# OLED.net
KiCad netlist of a schematic drawn in Altium Designer
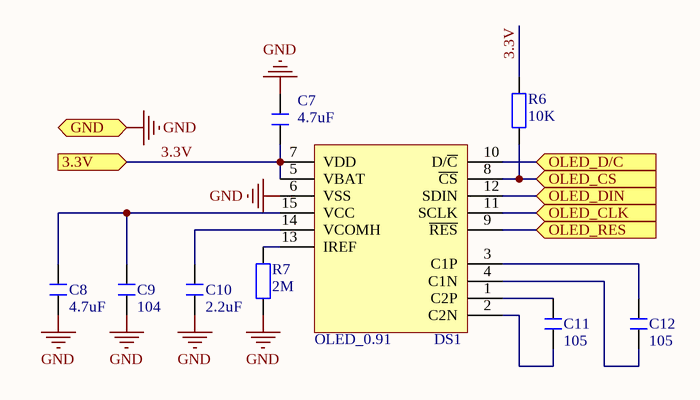
[diagram p0: OLED.SchDoc]

(export (version "E")
  (design (tool "Eeschema 10.0.6"))
  (components
    (comp (ref "C7")
      (value "4.7uF")
      (footprint "C 0603_L")
      (description "贴片电容")
      (libsource (lib "0.1 - 电阻-电容-电感") (part "C"))
    )
    (comp (ref "C8")
      (value "4.7uF")
      (footprint "C 0603_L")
      (description "贴片电容")
      (libsource (lib "0.1 - 电阻-电容-电感") (part "C"))
    )
    (comp (ref "C9")
      (value "104")
      (footprint "C 0603_L")
      (description "贴片电容")
      (libsource (lib "0.1 - 电阻-电容-电感") (part "C"))
    )
    (comp (ref "C10")
      (value "2.2uF")
      (footprint "C 0603_L")
      (description "贴片电容")
      (libsource (lib "0.1 - 电阻-电容-电感") (part "C"))
    )
    (comp (ref "C11")
      (value "105")
      (footprint "C 0603_L")
      (description "贴片电容")
      (libsource (lib "0.1 - 电阻-电容-电感") (part "C"))
    )
    (comp (ref "C12")
      (value "105")
      (footprint "C 0603_L")
      (description "贴片电容")
      (libsource (lib "0.1 - 电阻-电容-电感") (part "C"))
    )
    (comp (ref "DS1") (value "OLED_0.91") (footprint "OLED_0.91") (libsource (lib "显示器件") (part "OLED_0.91")))
    (comp (ref "R6")
      (value "10K")
      (footprint "R 0603_L")
      (description "贴片电阻")
      (libsource (lib "0.1 - 电阻-电容-电感") (part "R"))
    )
    (comp (ref "R7")
      (value "2M")
      (footprint "R 0603_L")
      (description "贴片电阻")
      (libsource (lib "0.1 - 电阻-电容-电感") (part "R"))
    )
  )
  (nets
    (net (code "1") (name "/3.3V") (class "Default")
      (node (ref "C7") (pin "1") (pinfunction "1_1") (pintype "passive"))
      (node (ref "DS1") (pin "5") (pinfunction "VBAT_5") (pintype "passive"))
      (node (ref "DS1") (pin "7") (pinfunction "VDD_7") (pintype "passive"))
      (node (ref "R6") (pin "2") (pinfunction "2_2") (pintype "passive"))
    )
    (net (code "2") (name "/OLED_CLK") (class "Default")
      (node (ref "DS1") (pin "11") (pinfunction "SCLK_11") (pintype "passive"))
    )
    (net (code "3") (name "/OLED_CS") (class "Default")
      (node (ref "DS1") (pin "8") (pinfunction "~{CS}_8") (pintype "passive"))
      (node (ref "R6") (pin "1") (pinfunction "1_1") (pintype "passive"))
    )
    (net (code "4") (name "/OLED_DIN") (class "Default")
      (node (ref "DS1") (pin "12") (pinfunction "SDIN_12") (pintype "passive"))
    )
    (net (code "5") (name "/OLED_D{slash}C") (class "Default")
      (node (ref "DS1") (pin "10") (pinfunction "D/~{C}_10") (pintype "passive"))
    )
    (net (code "6") (name "/OLED_RES") (class "Default")
      (node (ref "DS1") (pin "9") (pinfunction "~{RES}_9") (pintype "passive"))
    )
    (net (code "7") (name "GND") (class "Default")
      (node (ref "C10") (pin "1") (pinfunction "1_1") (pintype "passive"))
      (node (ref "C7") (pin "2") (pinfunction "2_2") (pintype "passive"))
      (node (ref "C8") (pin "1") (pinfunction "1_1") (pintype "passive"))
      (node (ref "C9") (pin "1") (pinfunction "1_1") (pintype "passive"))
      (node (ref "DS1") (pin "6") (pinfunction "VSS_6") (pintype "passive"))
      (node (ref "R7") (pin "1") (pinfunction "1_1") (pintype "passive"))
    )
    (net (code "8") (name "Net-(DS1-C1N)") (class "Default")
      (node (ref "C12") (pin "2") (pinfunction "2_2") (pintype "passive"))
      (node (ref "DS1") (pin "4") (pinfunction "C1N_4") (pintype "passive"))
    )
    (net (code "9") (name "Net-(DS1-C1P)") (class "Default")
      (node (ref "C12") (pin "1") (pinfunction "1_1") (pintype "passive"))
      (node (ref "DS1") (pin "3") (pinfunction "C1P_3") (pintype "passive"))
    )
    (net (code "10") (name "Net-(DS1-C2N)") (class "Default")
      (node (ref "C11") (pin "2") (pinfunction "2_2") (pintype "passive"))
      (node (ref "DS1") (pin "2") (pinfunction "C2N_2") (pintype "passive"))
    )
    (net (code "11") (name "Net-(DS1-C2P)") (class "Default")
      (node (ref "C11") (pin "1") (pinfunction "1_1") (pintype "passive"))
      (node (ref "DS1") (pin "1") (pinfunction "C2P_1") (pintype "passive"))
    )
    (net (code "12") (name "Net-(DS1-IREF)") (class "Default")
      (node (ref "DS1") (pin "13") (pinfunction "IREF_13") (pintype "passive"))
      (node (ref "R7") (pin "2") (pinfunction "2_2") (pintype "passive"))
    )
    (net (code "13") (name "Net-(DS1-VCC)") (class "Default")
      (node (ref "C8") (pin "2") (pinfunction "2_2") (pintype "passive"))
      (node (ref "C9") (pin "2") (pinfunction "2_2") (pintype "passive"))
      (node (ref "DS1") (pin "15") (pinfunction "VCC_15") (pintype "passive"))
    )
    (net (code "14") (name "Net-(DS1-VCOMH)") (class "Default")
      (node (ref "C10") (pin "2") (pinfunction "2_2") (pintype "passive"))
      (node (ref "DS1") (pin "14") (pinfunction "VCOMH_14") (pintype "passive"))
    )
  )
)
